# mpx.net
KiCad netlist of a schematic drawn in EAGLE
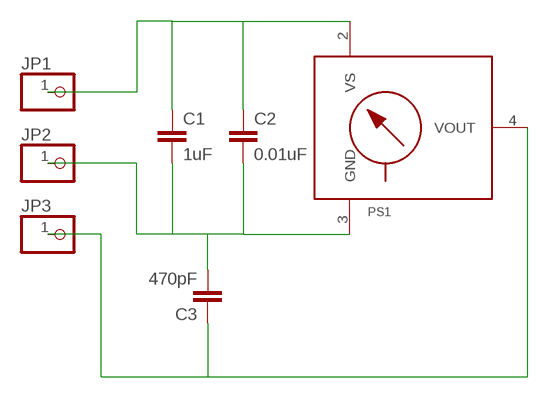
[diagram p0: schematic, sheet 1]

(export (version "E")
  (design (tool "Eeschema 10.0.6"))
  (components
    (comp (ref "C1")
      (value "1uF")
      (footprint "eagle-import:C050-024X044")
      (libsource (lib "eagle-import") (part "C-EU050-024X044"))
    )
    (comp (ref "C2")
      (value "0.01uF")
      (footprint "eagle-import:C050-024X044")
      (libsource (lib "eagle-import") (part "C-EU050-024X044"))
    )
    (comp (ref "C3")
      (value "470pF")
      (footprint "eagle-import:C050-024X044")
      (libsource (lib "eagle-import") (part "C-EU050-024X044"))
    )
    (comp (ref "JP1")
      (value "PINHD-1X1")
      (footprint "eagle-import:1X01")
      (libsource (lib "eagle-import") (part "PINHD-1X1"))
    )
    (comp (ref "JP2")
      (value "PINHD-1X1")
      (footprint "eagle-import:1X01")
      (libsource (lib "eagle-import") (part "PINHD-1X1"))
    )
    (comp (ref "JP3")
      (value "PINHD-1X1")
      (footprint "eagle-import:1X01")
      (libsource (lib "eagle-import") (part "PINHD-1X1"))
    )
    (comp (ref "PS1")
      (value "MPX-1369")
      (footprint "eagle-import:1369")
      (libsource (lib "eagle-import") (part "MPX-1369"))
    )
  )
  (nets
    (net (code "1") (name "Net-(PS1-GND)") (class "Default")
      (node (ref "C1") (pin "2") (pinfunction "2_2") (pintype "passive"))
      (node (ref "C2") (pin "2") (pinfunction "2_2") (pintype "passive"))
      (node (ref "C3") (pin "2") (pinfunction "2_2") (pintype "passive"))
      (node (ref "JP2") (pin "1") (pinfunction "1_1") (pintype "passive"))
      (node (ref "PS1") (pin "3") (pinfunction "GND_3") (pintype "power_in"))
    )
    (net (code "2") (name "Net-(PS1-VOUT)") (class "Default")
      (node (ref "C3") (pin "1") (pinfunction "1_1") (pintype "passive"))
      (node (ref "JP3") (pin "1") (pinfunction "1_1") (pintype "passive"))
      (node (ref "PS1") (pin "4") (pinfunction "VOUT_4") (pintype "output"))
    )
    (net (code "3") (name "Net-(PS1-VS)") (class "Default")
      (node (ref "C1") (pin "1") (pinfunction "1_1") (pintype "passive"))
      (node (ref "C2") (pin "1") (pinfunction "1_1") (pintype "passive"))
      (node (ref "JP1") (pin "1") (pinfunction "1_1") (pintype "passive"))
      (node (ref "PS1") (pin "2") (pinfunction "VS_2") (pintype "power_in"))
    )
    (net (code "4") (name "unconnected-(PS1-NC-Pad1)") (class "Default")
      (node (ref "PS1") (pin "1") (pinfunction "NC_1") (pintype "no_connect"))
    )
    (net (code "5") (name "unconnected-(PS1-NC-Pad5)") (class "Default")
      (node (ref "PS1") (pin "5") (pinfunction "NC_5") (pintype "no_connect"))
    )
    (net (code "6") (name "unconnected-(PS1-NC-Pad6)") (class "Default")
      (node (ref "PS1") (pin "6") (pinfunction "NC_6") (pintype "no_connect"))
    )
  )
)
